# Connectors.net
KiCad netlist of a schematic drawn in Altium Designer
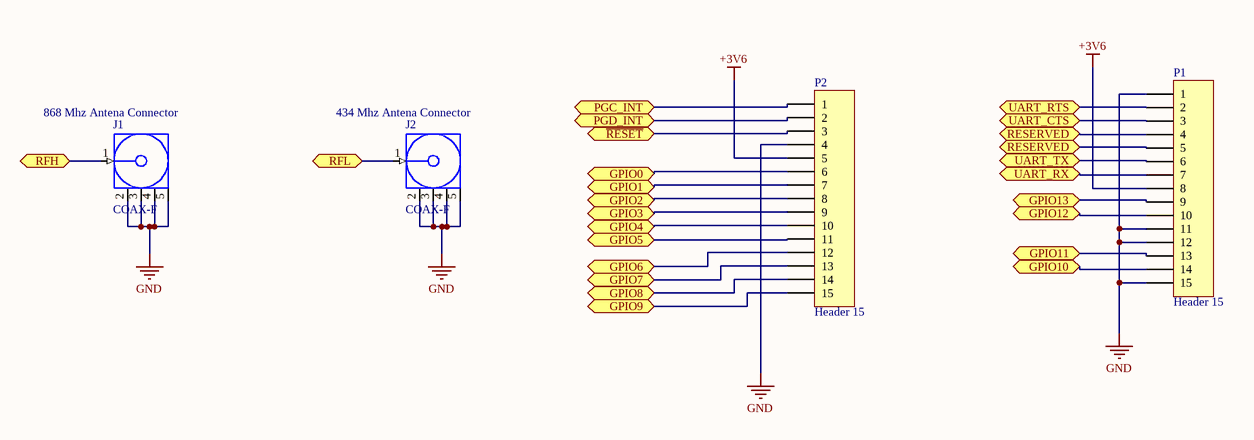
[diagram p0: Connectors.SchDoc]

(export (version "E")
  (design (tool "Eeschema 10.0.6"))
  (components
    (comp (ref "J1")
      (value "COAX-F")
      (footprint "MCX5.08-H5")
      (fields (field (name "PUBLISHER") "Altium Limited"))
      (libsource (lib "Miscellaneous Connectors") (part "COAX-F"))
    )
    (comp (ref "J2")
      (value "COAX-F")
      (footprint "MCX5.08-H5")
      (fields (field (name "PUBLISHER") "Altium Limited"))
      (libsource (lib "Miscellaneous Connectors") (part "COAX-F"))
    )
    (comp (ref "P1")
      (value "Header 15")
      (footprint "HDR1X15")
      (description "Header, 15-Pin")
      (fields (field (name "PUBLISHER") "Altium Limited"))
      (libsource (lib "Miscellaneous Connectors") (part "Header 15"))
    )
    (comp (ref "P2")
      (value "Header 15")
      (footprint "HDR1X15")
      (description "Header, 15-Pin")
      (fields (field (name "PUBLISHER") "Altium Limited"))
      (libsource (lib "Miscellaneous Connectors") (part "Header 15"))
    )
  )
  (nets
    (net (code "1") (name "+3V6") (class "Default")
      (node (ref "P1") (pin "8") (pinfunction "8_8") (pintype "passive"))
      (node (ref "P2") (pin "5") (pinfunction "5_5") (pintype "passive"))
    )
    (net (code "2") (name "/GPIO0") (class "Default")
      (node (ref "P2") (pin "6") (pinfunction "6_6") (pintype "passive"))
    )
    (net (code "3") (name "/GPIO1") (class "Default")
      (node (ref "P2") (pin "7") (pinfunction "7_7") (pintype "passive"))
    )
    (net (code "4") (name "/GPIO2") (class "Default")
      (node (ref "P2") (pin "8") (pinfunction "8_8") (pintype "passive"))
    )
    (net (code "5") (name "/GPIO3") (class "Default")
      (node (ref "P2") (pin "9") (pinfunction "9_9") (pintype "passive"))
    )
    (net (code "6") (name "/GPIO4") (class "Default")
      (node (ref "P2") (pin "10") (pinfunction "10_10") (pintype "passive"))
    )
    (net (code "7") (name "/GPIO5") (class "Default")
      (node (ref "P2") (pin "11") (pinfunction "11_11") (pintype "passive"))
    )
    (net (code "8") (name "/GPIO6") (class "Default")
      (node (ref "P2") (pin "12") (pinfunction "12_12") (pintype "passive"))
    )
    (net (code "9") (name "/GPIO7") (class "Default")
      (node (ref "P2") (pin "13") (pinfunction "13_13") (pintype "passive"))
    )
    (net (code "10") (name "/GPIO8") (class "Default")
      (node (ref "P2") (pin "14") (pinfunction "14_14") (pintype "passive"))
    )
    (net (code "11") (name "/GPIO9") (class "Default")
      (node (ref "P2") (pin "15") (pinfunction "15_15") (pintype "passive"))
    )
    (net (code "12") (name "/GPIO10") (class "Default")
      (node (ref "P1") (pin "14") (pinfunction "14_14") (pintype "passive"))
    )
    (net (code "13") (name "/GPIO11") (class "Default")
      (node (ref "P1") (pin "13") (pinfunction "13_13") (pintype "passive"))
    )
    (net (code "14") (name "/GPIO12") (class "Default")
      (node (ref "P1") (pin "10") (pinfunction "10_10") (pintype "passive"))
    )
    (net (code "15") (name "/GPIO13") (class "Default")
      (node (ref "P1") (pin "9") (pinfunction "9_9") (pintype "passive"))
    )
    (net (code "16") (name "/PGC_INT") (class "Default")
      (node (ref "P2") (pin "1") (pinfunction "1_1") (pintype "passive"))
    )
    (net (code "17") (name "/PGD_INT") (class "Default")
      (node (ref "P2") (pin "2") (pinfunction "2_2") (pintype "passive"))
    )
    (net (code "18") (name "/RESERVED") (class "Default")
      (node (ref "P1") (pin "4") (pinfunction "4_4") (pintype "passive"))
      (node (ref "P1") (pin "5") (pinfunction "5_5") (pintype "passive"))
    )
    (net (code "19") (name "/RFH") (class "Default")
      (node (ref "J1") (pin "1") (pinfunction "Signal_1") (pintype "input"))
    )
    (net (code "20") (name "/RFL") (class "Default")
      (node (ref "J2") (pin "1") (pinfunction "Signal_1") (pintype "input"))
    )
    (net (code "21") (name "/UART_CTS") (class "Default")
      (node (ref "P1") (pin "3") (pinfunction "3_3") (pintype "passive"))
    )
    (net (code "22") (name "/UART_RTS") (class "Default")
      (node (ref "P1") (pin "2") (pinfunction "2_2") (pintype "passive"))
    )
    (net (code "23") (name "/UART_RX") (class "Default")
      (node (ref "P1") (pin "7") (pinfunction "7_7") (pintype "passive"))
    )
    (net (code "24") (name "/UART_TX") (class "Default")
      (node (ref "P1") (pin "6") (pinfunction "6_6") (pintype "passive"))
    )
    (net (code "25") (name "/~{RESET}") (class "Default")
      (node (ref "P2") (pin "3") (pinfunction "3_3") (pintype "passive"))
    )
    (net (code "26") (name "GND") (class "Default")
      (node (ref "J1") (pin "2") (pinfunction "GND_2") (pintype "power_in"))
      (node (ref "J1") (pin "3") (pinfunction "GND_3") (pintype "power_in"))
      (node (ref "J1") (pin "4") (pinfunction "GND_4") (pintype "power_in"))
      (node (ref "J1") (pin "5") (pinfunction "GND_5") (pintype "power_in"))
      (node (ref "J2") (pin "2") (pinfunction "GND_2") (pintype "power_in"))
      (node (ref "J2") (pin "3") (pinfunction "GND_3") (pintype "power_in"))
      (node (ref "J2") (pin "4") (pinfunction "GND_4") (pintype "power_in"))
      (node (ref "J2") (pin "5") (pinfunction "GND_5") (pintype "power_in"))
      (node (ref "P1") (pin "1") (pinfunction "1_1") (pintype "passive"))
      (node (ref "P1") (pin "11") (pinfunction "11_11") (pintype "passive"))
      (node (ref "P1") (pin "12") (pinfunction "12_12") (pintype "passive"))
      (node (ref "P1") (pin "15") (pinfunction "15_15") (pintype "passive"))
      (node (ref "P2") (pin "4") (pinfunction "4_4") (pintype "passive"))
    )
  )
)
